# Sensor_Module_0x12_U-Value_v1.net
KiCad netlist of a schematic drawn in EAGLE
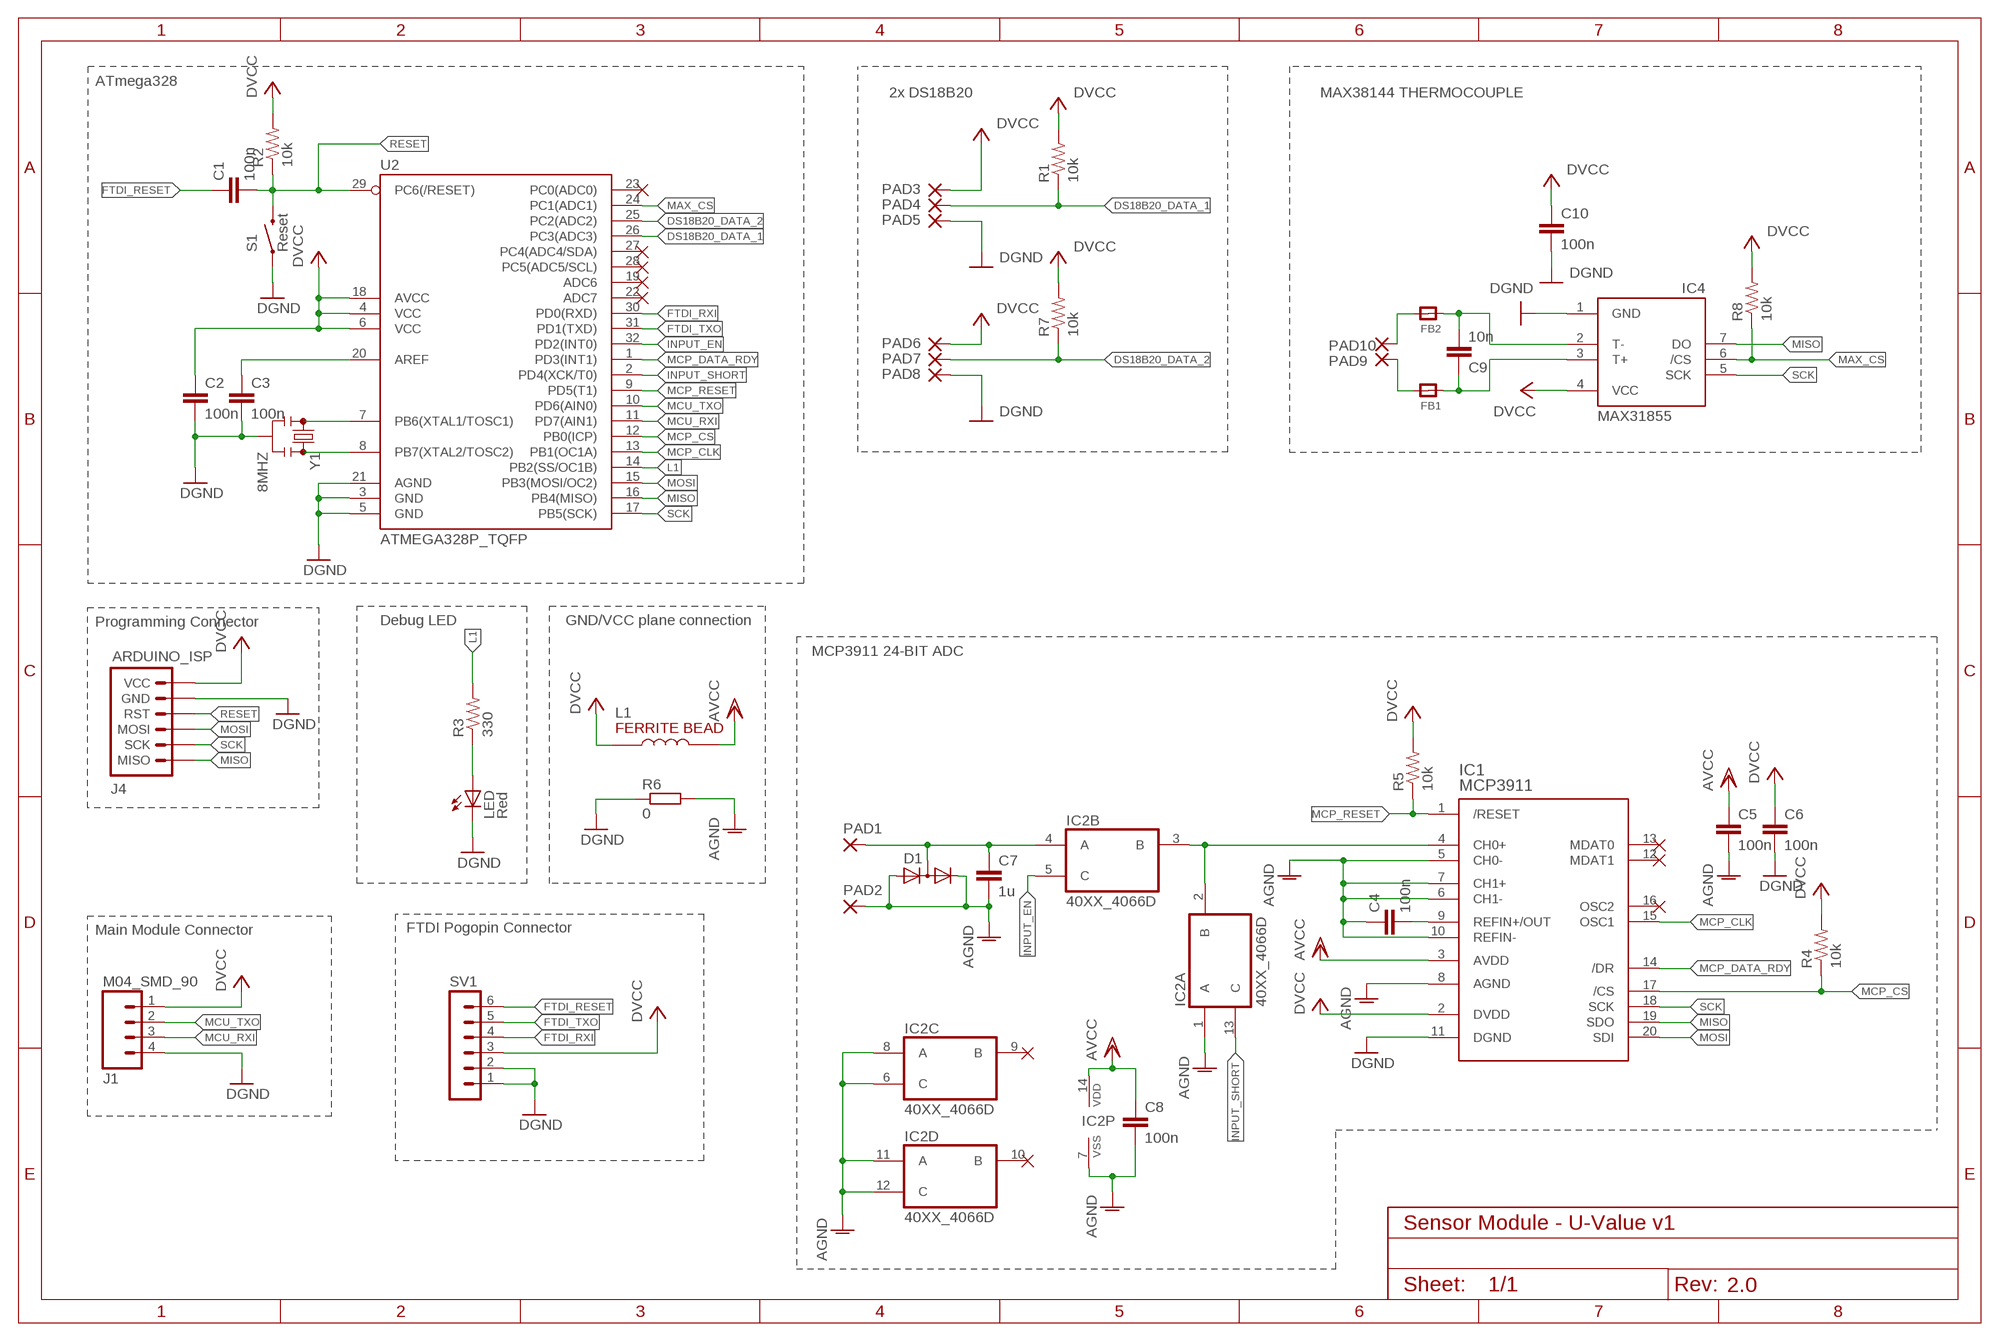
[diagram p0: schematic, sheet 1]

(export (version "E")
  (design (tool "Eeschema 10.0.6"))
  (components
    (comp (ref "C1")
      (value "100n")
      (footprint "eagle-import:C0805")
      (libsource (lib "eagle-import") (part "C"))
    )
    (comp (ref "C2")
      (value "100n")
      (footprint "eagle-import:C0805")
      (libsource (lib "eagle-import") (part "C"))
    )
    (comp (ref "C3")
      (value "100n")
      (footprint "eagle-import:C0805")
      (libsource (lib "eagle-import") (part "C"))
    )
    (comp (ref "C4")
      (value "100n")
      (footprint "eagle-import:C0805")
      (libsource (lib "eagle-import") (part "C"))
    )
    (comp (ref "C5")
      (value "100n")
      (footprint "eagle-import:C0805")
      (libsource (lib "eagle-import") (part "C"))
    )
    (comp (ref "C6")
      (value "100n")
      (footprint "eagle-import:C0805")
      (libsource (lib "eagle-import") (part "C"))
    )
    (comp (ref "C7")
      (value "1u")
      (footprint "eagle-import:C0805")
      (libsource (lib "eagle-import") (part "C"))
    )
    (comp (ref "C8")
      (value "100n")
      (footprint "eagle-import:C0805")
      (libsource (lib "eagle-import") (part "C"))
    )
    (comp (ref "C9")
      (value "10n")
      (footprint "eagle-import:C0805")
      (libsource (lib "eagle-import") (part "C"))
    )
    (comp (ref "C10")
      (value "100n")
      (footprint "eagle-import:C0805")
      (libsource (lib "eagle-import") (part "C"))
    )
    (comp (ref "D1")
      (value "LEDXLAMP_BAV99")
      (footprint "eagle-import:LEDXLAMP_SOT23")
      (libsource (lib "eagle-import") (part "LEDXLAMP_BAV99"))
    )
    (comp (ref "FB1")
      (value "MICROBUILDER_FERRITE_0805MP")
      (footprint "eagle-import:MICROBUILDER__0805MP")
      (libsource (lib "eagle-import") (part "MICROBUILDER_FERRITE_0805MP"))
    )
    (comp (ref "FB2")
      (value "MICROBUILDER_FERRITE_0805MP")
      (footprint "eagle-import:MICROBUILDER__0805MP")
      (libsource (lib "eagle-import") (part "MICROBUILDER_FERRITE_0805MP"))
    )
    (comp (ref "IC1")
      (value "MCP3911")
      (footprint "eagle-import:HEATFLOW_SSOP20")
      (libsource (lib "eagle-import") (part "HEATFLOW_MCP3911A0-E/SS"))
    )
    (comp (ref "IC2")
      (value "40XX_4066D")
      (footprint "eagle-import:40XX_SO14")
      (libsource (lib "eagle-import") (part "40XX_4066D"))
    )
    (comp (ref "IC4")
      (value "MAX31855")
      (footprint "eagle-import:ADAFRUIT_SO08")
      (libsource (lib "eagle-import") (part "ADAFRUIT_MAX31855"))
    )
    (comp (ref "J1")
      (value "M04_SMD_90")
      (footprint "eagle-import:M04_SMD_90")
      (libsource (lib "eagle-import") (part "M04_SMD_90"))
    )
    (comp (ref "J4")
      (value "ARDUINO_ISP")
      (footprint "eagle-import:M-2X3")
      (libsource (lib "eagle-import") (part "ARDUINO_ISP"))
    )
    (comp (ref "L1")
      (value "HEATFLOW2_74279220601")
      (footprint "eagle-import:HEATFLOW2_0805")
      (libsource (lib "eagle-import") (part "HEATFLOW2_74279220601"))
    )
    (comp (ref "LED")
      (value "Red")
      (footprint "eagle-import:SML0805")
      (libsource (lib "eagle-import") (part "LEDSML0805"))
    )
    (comp (ref "PAD1")
      (value "WIREPADSMD1,27-254")
      (footprint "eagle-import:SMD1,27-2,54")
      (libsource (lib "eagle-import") (part "WIREPADSMD1,27-254"))
    )
    (comp (ref "PAD2")
      (value "WIREPADSMD1,27-254")
      (footprint "eagle-import:SMD1,27-2,54")
      (libsource (lib "eagle-import") (part "WIREPADSMD1,27-254"))
    )
    (comp (ref "PAD3")
      (value "WIREPADSMD1,27-254")
      (footprint "eagle-import:SMD1,27-2,54")
      (libsource (lib "eagle-import") (part "WIREPADSMD1,27-254"))
    )
    (comp (ref "PAD4")
      (value "WIREPADSMD1,27-254")
      (footprint "eagle-import:SMD1,27-2,54")
      (libsource (lib "eagle-import") (part "WIREPADSMD1,27-254"))
    )
    (comp (ref "PAD5")
      (value "WIREPADSMD1,27-254")
      (footprint "eagle-import:SMD1,27-2,54")
      (libsource (lib "eagle-import") (part "WIREPADSMD1,27-254"))
    )
    (comp (ref "PAD6")
      (value "WIREPADSMD1,27-254")
      (footprint "eagle-import:SMD1,27-2,54")
      (libsource (lib "eagle-import") (part "WIREPADSMD1,27-254"))
    )
    (comp (ref "PAD7")
      (value "WIREPADSMD1,27-254")
      (footprint "eagle-import:SMD1,27-2,54")
      (libsource (lib "eagle-import") (part "WIREPADSMD1,27-254"))
    )
    (comp (ref "PAD8")
      (value "WIREPADSMD1,27-254")
      (footprint "eagle-import:SMD1,27-2,54")
      (libsource (lib "eagle-import") (part "WIREPADSMD1,27-254"))
    )
    (comp (ref "PAD9")
      (value "WIREPADSMD1,27-254")
      (footprint "eagle-import:SMD1,27-2,54")
      (libsource (lib "eagle-import") (part "WIREPADSMD1,27-254"))
    )
    (comp (ref "PAD10")
      (value "WIREPADSMD1,27-254")
      (footprint "eagle-import:SMD1,27-2,54")
      (libsource (lib "eagle-import") (part "WIREPADSMD1,27-254"))
    )
    (comp (ref "R1")
      (value "10k")
      (footprint "eagle-import:0805")
      (libsource (lib "eagle-import") (part "RESISTOR0805-RES"))
    )
    (comp (ref "R2")
      (value "10k")
      (footprint "eagle-import:0805")
      (libsource (lib "eagle-import") (part "RESISTOR0805-RES"))
    )
    (comp (ref "R3")
      (value "330")
      (footprint "eagle-import:0805")
      (libsource (lib "eagle-import") (part "RESISTOR0805-RES"))
    )
    (comp (ref "R4")
      (value "10k")
      (footprint "eagle-import:0805")
      (libsource (lib "eagle-import") (part "RESISTOR0805-RES"))
    )
    (comp (ref "R5")
      (value "10k")
      (footprint "eagle-import:0805")
      (libsource (lib "eagle-import") (part "RESISTOR0805-RES"))
    )
    (comp (ref "R6")
      (value "0")
      (footprint "eagle-import:RESISTOR_M0805")
      (libsource (lib "eagle-import") (part "RESISTOR_R-EU_M0805"))
    )
    (comp (ref "R7")
      (value "10k")
      (footprint "eagle-import:0805")
      (libsource (lib "eagle-import") (part "RESISTOR0805-RES"))
    )
    (comp (ref "R8")
      (value "10k")
      (footprint "eagle-import:0805")
      (libsource (lib "eagle-import") (part "RESISTOR0805-RES"))
    )
    (comp (ref "S1")
      (value "Reset")
      (footprint "eagle-import:M-PUSHBUTTON-SMD")
      (libsource (lib "eagle-import") (part "PUSHBUTTON"))
    )
    (comp (ref "SV1")
      (value "MA06-1")
      (footprint "eagle-import:MA06-1")
      (libsource (lib "eagle-import") (part "MA06-1"))
    )
    (comp (ref "U2")
      (value "ATMEGA328P_TQFP")
      (footprint "eagle-import:TQFP32-08")
      (libsource (lib "eagle-import") (part "ATMEGA328P_TQFP"))
    )
    (comp (ref "Y1")
      (value "8MHZ")
      (footprint "eagle-import:RESONATOR-SMD")
      (libsource (lib "eagle-import") (part "RESONATOR8MHZ"))
    )
  )
  (nets
    (net (code "1") (name "AGND") (class "Default")
      (node (ref "C4") (pin "1") (pinfunction "1_1") (pintype "passive"))
      (node (ref "C5") (pin "2") (pinfunction "2_2") (pintype "passive"))
      (node (ref "C7") (pin "2") (pinfunction "2_2") (pintype "passive"))
      (node (ref "C8") (pin "2") (pinfunction "2_2") (pintype "passive"))
      (node (ref "D1") (pin "1") (pinfunction "A_1") (pintype "passive"))
      (node (ref "D1") (pin "2") (pinfunction "C_2") (pintype "passive"))
      (node (ref "IC1") (pin "10") (pinfunction "REFIN-_10") (pintype "bidirectional"))
      (node (ref "IC1") (pin "5") (pinfunction "CH0-_5") (pintype "bidirectional"))
      (node (ref "IC1") (pin "6") (pinfunction "CH1-_6") (pintype "bidirectional"))
      (node (ref "IC1") (pin "7") (pinfunction "CH1+_7") (pintype "bidirectional"))
      (node (ref "IC1") (pin "8") (pinfunction "AGND_8") (pintype "bidirectional"))
      (node (ref "IC2") (pin "1") (pinfunction "A_1") (pintype "tri_state"))
      (node (ref "IC2") (pin "11") (pinfunction "A_11") (pintype "tri_state"))
      (node (ref "IC2") (pin "12") (pinfunction "C_12") (pintype "input"))
      (node (ref "IC2") (pin "6") (pinfunction "C_6") (pintype "input"))
      (node (ref "IC2") (pin "7") (pinfunction "VSS_7") (pintype "power_in"))
      (node (ref "IC2") (pin "8") (pinfunction "A_8") (pintype "tri_state"))
      (node (ref "PAD2") (pin "1") (pinfunction "P_1") (pintype "passive"))
      (node (ref "R6") (pin "2") (pinfunction "2_2") (pintype "passive"))
    )
    (net (code "2") (name "AVCC") (class "Default")
      (node (ref "C5") (pin "1") (pinfunction "1_1") (pintype "passive"))
      (node (ref "C8") (pin "1") (pinfunction "1_1") (pintype "passive"))
      (node (ref "IC1") (pin "3") (pinfunction "AVDD_3") (pintype "bidirectional"))
      (node (ref "IC2") (pin "14") (pinfunction "VDD_14") (pintype "power_in"))
      (node (ref "L1") (pin "2") (pinfunction "P$2_2") (pintype "bidirectional"))
    )
    (net (code "3") (name "DGND") (class "Default")
      (node (ref "C10") (pin "2") (pinfunction "2_2") (pintype "passive"))
      (node (ref "C2") (pin "2") (pinfunction "2_2") (pintype "passive"))
      (node (ref "C3") (pin "2") (pinfunction "2_2") (pintype "passive"))
      (node (ref "C6") (pin "2") (pinfunction "2_2") (pintype "passive"))
      (node (ref "IC1") (pin "11") (pinfunction "DGND_11") (pintype "bidirectional"))
      (node (ref "IC4") (pin "1") (pinfunction "GND_1") (pintype "power_in"))
      (node (ref "J1") (pin "4") (pinfunction "4_4") (pintype "passive"))
      (node (ref "J4") (pin "P$5") (pinfunction "GND_P$5") (pintype "passive"))
      (node (ref "LED") (pin "C") (pinfunction "C_C") (pintype "passive"))
      (node (ref "PAD5") (pin "1") (pinfunction "P_1") (pintype "passive"))
      (node (ref "PAD8") (pin "1") (pinfunction "P_1") (pintype "passive"))
      (node (ref "R6") (pin "1") (pinfunction "1_1") (pintype "passive"))
      (node (ref "S1") (pin "1") (pinfunction "LEFT_1") (pintype "passive"))
      (node (ref "S1") (pin "2") (pinfunction "LEFT_2") (pintype "passive"))
      (node (ref "SV1") (pin "1") (pinfunction "1_1") (pintype "passive"))
      (node (ref "SV1") (pin "2") (pinfunction "2_2") (pintype "passive"))
      (node (ref "U2") (pin "21") (pinfunction "AGND_21") (pintype "bidirectional"))
      (node (ref "U2") (pin "3") (pinfunction "GND_3") (pintype "bidirectional"))
      (node (ref "U2") (pin "5") (pinfunction "GND_5") (pintype "bidirectional"))
      (node (ref "Y1") (pin "2") (pinfunction "2_2") (pintype "passive"))
    )
    (net (code "4") (name "DS18B20_DATA_1") (class "Default")
      (node (ref "PAD4") (pin "1") (pinfunction "P_1") (pintype "passive"))
      (node (ref "R1") (pin "1") (pinfunction "1_1") (pintype "passive"))
      (node (ref "U2") (pin "26") (pinfunction "PC3(ADC3)_26") (pintype "bidirectional"))
    )
    (net (code "5") (name "DS18B20_DATA_2") (class "Default")
      (node (ref "PAD7") (pin "1") (pinfunction "P_1") (pintype "passive"))
      (node (ref "R7") (pin "1") (pinfunction "1_1") (pintype "passive"))
      (node (ref "U2") (pin "25") (pinfunction "PC2(ADC2)_25") (pintype "bidirectional"))
    )
    (net (code "6") (name "DVCC") (class "Default")
      (node (ref "C10") (pin "1") (pinfunction "1_1") (pintype "passive"))
      (node (ref "C2") (pin "1") (pinfunction "1_1") (pintype "passive"))
      (node (ref "C6") (pin "1") (pinfunction "1_1") (pintype "passive"))
      (node (ref "IC1") (pin "2") (pinfunction "DVDD_2") (pintype "bidirectional"))
      (node (ref "IC4") (pin "4") (pinfunction "VCC_4") (pintype "power_in"))
      (node (ref "J1") (pin "1") (pinfunction "1_1") (pintype "passive"))
      (node (ref "J4") (pin "P$6") (pinfunction "VCC_P$6") (pintype "passive"))
      (node (ref "L1") (pin "1") (pinfunction "P$1_1") (pintype "bidirectional"))
      (node (ref "PAD3") (pin "1") (pinfunction "P_1") (pintype "passive"))
      (node (ref "PAD6") (pin "1") (pinfunction "P_1") (pintype "passive"))
      (node (ref "R1") (pin "2") (pinfunction "2_2") (pintype "passive"))
      (node (ref "R2") (pin "2") (pinfunction "2_2") (pintype "passive"))
      (node (ref "R4") (pin "2") (pinfunction "2_2") (pintype "passive"))
      (node (ref "R5") (pin "2") (pinfunction "2_2") (pintype "passive"))
      (node (ref "R7") (pin "2") (pinfunction "2_2") (pintype "passive"))
      (node (ref "R8") (pin "2") (pinfunction "2_2") (pintype "passive"))
      (node (ref "SV1") (pin "3") (pinfunction "3_3") (pintype "passive"))
      (node (ref "U2") (pin "18") (pinfunction "AVCC_18") (pintype "bidirectional"))
      (node (ref "U2") (pin "4") (pinfunction "VCC_4") (pintype "bidirectional"))
      (node (ref "U2") (pin "6") (pinfunction "VCC_6") (pintype "bidirectional"))
    )
    (net (code "7") (name "FTDI_RESET") (class "Default")
      (node (ref "C1") (pin "1") (pinfunction "1_1") (pintype "passive"))
      (node (ref "SV1") (pin "6") (pinfunction "6_6") (pintype "passive"))
    )
    (net (code "8") (name "FTDI_RXI") (class "Default")
      (node (ref "SV1") (pin "4") (pinfunction "4_4") (pintype "passive"))
      (node (ref "U2") (pin "30") (pinfunction "PD0(RXD)_30") (pintype "bidirectional"))
    )
    (net (code "9") (name "FTDI_TXO") (class "Default")
      (node (ref "SV1") (pin "5") (pinfunction "5_5") (pintype "passive"))
      (node (ref "U2") (pin "31") (pinfunction "PD1(TXD)_31") (pintype "bidirectional"))
    )
    (net (code "10") (name "INPUT_EN") (class "Default")
      (node (ref "IC2") (pin "5") (pinfunction "C_5") (pintype "input"))
      (node (ref "U2") (pin "32") (pinfunction "PD2(INT0)_32") (pintype "bidirectional"))
    )
    (net (code "11") (name "INPUT_SHORT") (class "Default")
      (node (ref "IC2") (pin "13") (pinfunction "C_13") (pintype "input"))
      (node (ref "U2") (pin "2") (pinfunction "PD4(XCK/T0)_2") (pintype "bidirectional"))
    )
    (net (code "12") (name "L1") (class "Default")
      (node (ref "R3") (pin "2") (pinfunction "2_2") (pintype "passive"))
      (node (ref "U2") (pin "14") (pinfunction "PB2(SS/OC1B)_14") (pintype "bidirectional"))
    )
    (net (code "13") (name "MAX_CS") (class "Default")
      (node (ref "IC4") (pin "6") (pinfunction "/CS_6") (pintype "input"))
      (node (ref "R8") (pin "1") (pinfunction "1_1") (pintype "passive"))
      (node (ref "U2") (pin "24") (pinfunction "PC1(ADC1)_24") (pintype "bidirectional"))
    )
    (net (code "14") (name "MCP_CLK") (class "Default")
      (node (ref "IC1") (pin "15") (pinfunction "OSC1_15") (pintype "bidirectional"))
      (node (ref "U2") (pin "13") (pinfunction "PB1(OC1A)_13") (pintype "bidirectional"))
    )
    (net (code "15") (name "MCP_CS") (class "Default")
      (node (ref "IC1") (pin "17") (pinfunction "/CS_17") (pintype "bidirectional"))
      (node (ref "R4") (pin "1") (pinfunction "1_1") (pintype "passive"))
      (node (ref "U2") (pin "12") (pinfunction "PB0(ICP)_12") (pintype "bidirectional"))
    )
    (net (code "16") (name "MCP_DATA_RDY") (class "Default")
      (node (ref "IC1") (pin "14") (pinfunction "/DR_14") (pintype "bidirectional"))
      (node (ref "U2") (pin "1") (pinfunction "PD3(INT1)_1") (pintype "bidirectional"))
    )
    (net (code "17") (name "MCP_RESET") (class "Default")
      (node (ref "IC1") (pin "1") (pinfunction "/RESET_1") (pintype "bidirectional"))
      (node (ref "R5") (pin "1") (pinfunction "1_1") (pintype "passive"))
      (node (ref "U2") (pin "9") (pinfunction "PD5(T1)_9") (pintype "bidirectional"))
    )
    (net (code "18") (name "MCU_RXI") (class "Default")
      (node (ref "J1") (pin "3") (pinfunction "3_3") (pintype "passive"))
      (node (ref "U2") (pin "11") (pinfunction "PD7(AIN1)_11") (pintype "bidirectional"))
    )
    (net (code "19") (name "MCU_TXO") (class "Default")
      (node (ref "J1") (pin "2") (pinfunction "2_2") (pintype "passive"))
      (node (ref "U2") (pin "10") (pinfunction "PD6(AIN0)_10") (pintype "bidirectional"))
    )
    (net (code "20") (name "MISO") (class "Default")
      (node (ref "IC1") (pin "19") (pinfunction "SDO_19") (pintype "bidirectional"))
      (node (ref "IC4") (pin "7") (pinfunction "DO_7") (pintype "output"))
      (node (ref "J4") (pin "P$1") (pinfunction "MISO_P$1") (pintype "passive"))
      (node (ref "U2") (pin "16") (pinfunction "PB4(MISO)_16") (pintype "bidirectional"))
    )
    (net (code "21") (name "MOSI") (class "Default")
      (node (ref "IC1") (pin "20") (pinfunction "SDI_20") (pintype "bidirectional"))
      (node (ref "J4") (pin "P$3") (pinfunction "MOSI_P$3") (pintype "passive"))
      (node (ref "U2") (pin "15") (pinfunction "PB3(MOSI/OC2)_15") (pintype "bidirectional"))
    )
    (net (code "22") (name "Net-(D1-AC)") (class "Default")
      (node (ref "C7") (pin "1") (pinfunction "1_1") (pintype "passive"))
      (node (ref "D1") (pin "3") (pinfunction "AC_3") (pintype "passive"))
      (node (ref "IC2") (pin "4") (pinfunction "A_4") (pintype "tri_state"))
      (node (ref "PAD1") (pin "1") (pinfunction "P_1") (pintype "passive"))
    )
    (net (code "23") (name "Net-(FB1-P$1)") (class "Default")
      (node (ref "FB1") (pin "1") (pinfunction "P$1_1") (pintype "passive"))
      (node (ref "PAD9") (pin "1") (pinfunction "P_1") (pintype "passive"))
    )
    (net (code "24") (name "Net-(FB1-P$2)") (class "Default")
      (node (ref "C9") (pin "1") (pinfunction "1_1") (pintype "passive"))
      (node (ref "FB1") (pin "2") (pinfunction "P$2_2") (pintype "passive"))
      (node (ref "IC4") (pin "3") (pinfunction "T+_3") (pintype "input"))
    )
    (net (code "25") (name "Net-(FB2-P$1)") (class "Default")
      (node (ref "FB2") (pin "1") (pinfunction "P$1_1") (pintype "passive"))
      (node (ref "PAD10") (pin "1") (pinfunction "P_1") (pintype "passive"))
    )
    (net (code "26") (name "Net-(FB2-P$2)") (class "Default")
      (node (ref "C9") (pin "2") (pinfunction "2_2") (pintype "passive"))
      (node (ref "FB2") (pin "2") (pinfunction "P$2_2") (pintype "passive"))
      (node (ref "IC4") (pin "2") (pinfunction "T-_2") (pintype "input"))
    )
    (net (code "27") (name "Net-(IC1-CH0+)") (class "Default")
      (node (ref "IC1") (pin "4") (pinfunction "CH0+_4") (pintype "bidirectional"))
      (node (ref "IC2") (pin "2") (pinfunction "B_2") (pintype "tri_state"))
      (node (ref "IC2") (pin "3") (pinfunction "B_3") (pintype "tri_state"))
    )
    (net (code "28") (name "Net-(IC1-REFIN+{slash}OUT)") (class "Default")
      (node (ref "C4") (pin "2") (pinfunction "2_2") (pintype "passive"))
      (node (ref "IC1") (pin "9") (pinfunction "REFIN+/OUT_9") (pintype "bidirectional"))
    )
    (net (code "29") (name "Net-(LED-PadA)") (class "Default")
      (node (ref "LED") (pin "A") (pinfunction "A_A") (pintype "passive"))
      (node (ref "R3") (pin "1") (pinfunction "1_1") (pintype "passive"))
    )
    (net (code "30") (name "Net-(U2-AREF)") (class "Default")
      (node (ref "C3") (pin "1") (pinfunction "1_1") (pintype "passive"))
      (node (ref "U2") (pin "20") (pinfunction "AREF_20") (pintype "bidirectional"))
    )
    (net (code "31") (name "Net-(U2-PB6(XTAL1{slash}TOSC1))") (class "Default")
      (node (ref "U2") (pin "7") (pinfunction "PB6(XTAL1/TOSC1)_7") (pintype "bidirectional"))
      (node (ref "Y1") (pin "1") (pinfunction "1_1") (pintype "passive"))
    )
    (net (code "32") (name "Net-(U2-PB7(XTAL2{slash}TOSC2))") (class "Default")
      (node (ref "U2") (pin "8") (pinfunction "PB7(XTAL2/TOSC2)_8") (pintype "bidirectional"))
      (node (ref "Y1") (pin "3") (pinfunction "3_3") (pintype "passive"))
    )
    (net (code "33") (name "RESET") (class "Default")
      (node (ref "C1") (pin "2") (pinfunction "2_2") (pintype "passive"))
      (node (ref "J4") (pin "P$4") (pinfunction "RST_P$4") (pintype "passive"))
      (node (ref "R2") (pin "1") (pinfunction "1_1") (pintype "passive"))
      (node (ref "S1") (pin "3") (pinfunction "RIGHT_3") (pintype "passive"))
      (node (ref "S1") (pin "4") (pinfunction "RIGHT_4") (pintype "passive"))
      (node (ref "U2") (pin "29") (pinfunction "PC6(/RESET)_29") (pintype "bidirectional"))
    )
    (net (code "34") (name "SCK") (class "Default")
      (node (ref "IC1") (pin "18") (pinfunction "SCK_18") (pintype "bidirectional"))
      (node (ref "IC4") (pin "5") (pinfunction "SCK_5") (pintype "input"))
      (node (ref "J4") (pin "P$2") (pinfunction "SCK_P$2") (pintype "passive"))
      (node (ref "U2") (pin "17") (pinfunction "PB5(SCK)_17") (pintype "bidirectional"))
    )
    (net (code "35") (name "unconnected-(IC1-MDAT0-Pad13)") (class "Default")
      (node (ref "IC1") (pin "13") (pinfunction "MDAT0_13") (pintype "bidirectional"))
    )
    (net (code "36") (name "unconnected-(IC1-MDAT1-Pad12)") (class "Default")
      (node (ref "IC1") (pin "12") (pinfunction "MDAT1_12") (pintype "bidirectional"))
    )
    (net (code "37") (name "unconnected-(IC1-OSC2-Pad16)") (class "Default")
      (node (ref "IC1") (pin "16") (pinfunction "OSC2_16") (pintype "bidirectional"))
    )
    (net (code "38") (name "unconnected-(IC2C-B-Pad9)") (class "Default")
      (node (ref "IC2") (pin "9") (pinfunction "B_9") (pintype "tri_state"))
    )
    (net (code "39") (name "unconnected-(IC2D-B-Pad10)") (class "Default")
      (node (ref "IC2") (pin "10") (pinfunction "B_10") (pintype "tri_state"))
    )
    (net (code "40") (name "unconnected-(U2-ADC6-Pad19)") (class "Default")
      (node (ref "U2") (pin "19") (pinfunction "ADC6_19") (pintype "bidirectional"))
    )
    (net (code "41") (name "unconnected-(U2-ADC7-Pad22)") (class "Default")
      (node (ref "U2") (pin "22") (pinfunction "ADC7_22") (pintype "bidirectional"))
    )
    (net (code "42") (name "unconnected-(U2-PC0(ADC0)-Pad23)") (class "Default")
      (node (ref "U2") (pin "23") (pinfunction "PC0(ADC0)_23") (pintype "bidirectional"))
    )
    (net (code "43") (name "unconnected-(U2-PC4(ADC4{slash}SDA)-Pad27)") (class "Default")
      (node (ref "U2") (pin "27") (pinfunction "PC4(ADC4/SDA)_27") (pintype "bidirectional"))
    )
    (net (code "44") (name "unconnected-(U2-PC5(ADC5{slash}SCL)-Pad28)") (class "Default")
      (node (ref "U2") (pin "28") (pinfunction "PC5(ADC5/SCL)_28") (pintype "bidirectional"))
    )
  )
)
